# Sheet_Top_Back.net
KiCad netlist of a schematic drawn in Altium Designer
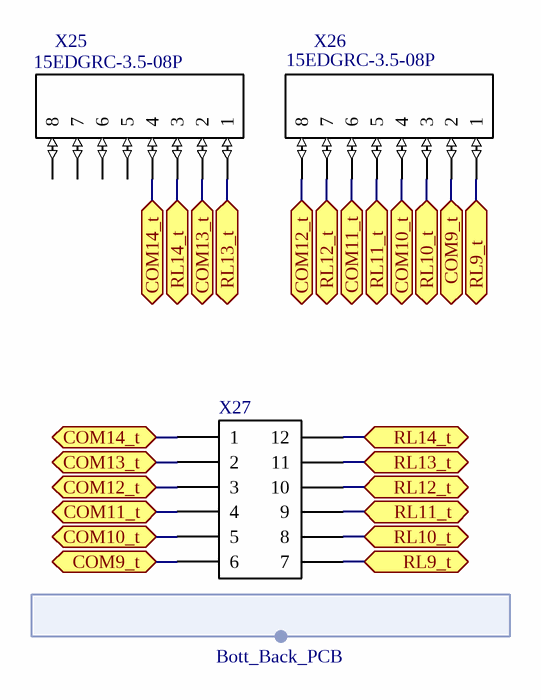
[diagram p0: Sheet_Top_Back.SchDoc]

(export (version "E")
  (design (tool "Eeschema 10.0.6"))
  (components
    (comp (ref "X25")
      (value "15EDGRC-3.5-08P")
      (footprint "MC_3.5_8")
      (description "Connector 3.5mm")
      (libsource (lib "Connect") (part "MC_3.5_8"))
    )
    (comp (ref "X26")
      (value "15EDGRC-3.5-08P")
      (footprint "MC_3.5_8")
      (description "Connector 3.5mm")
      (libsource (lib "Connect") (part "MC_3.5_8"))
    )
    (comp (ref "X27")
      (value "PBS2-12")
      (footprint "PLS2-12")
      (description "Header, 12-Pin")
      (libsource (lib "Connect") (part "PLS2-12"))
    )
  )
  (nets
    (net (code "1") (name "/COM9_t") (class "Default")
      (node (ref "X26") (pin "2") (pinfunction "2_2") (pintype "bidirectional"))
      (node (ref "X27") (pin "6") (pinfunction "6_6") (pintype "passive"))
    )
    (net (code "2") (name "/COM10_t") (class "Default")
      (node (ref "X26") (pin "4") (pinfunction "4_4") (pintype "bidirectional"))
      (node (ref "X27") (pin "5") (pinfunction "5_5") (pintype "passive"))
    )
    (net (code "3") (name "/COM11_t") (class "Default")
      (node (ref "X26") (pin "6") (pinfunction "6_6") (pintype "bidirectional"))
      (node (ref "X27") (pin "4") (pinfunction "4_4") (pintype "passive"))
    )
    (net (code "4") (name "/COM12_t") (class "Default")
      (node (ref "X26") (pin "8") (pinfunction "8_8") (pintype "bidirectional"))
      (node (ref "X27") (pin "3") (pinfunction "3_3") (pintype "passive"))
    )
    (net (code "5") (name "/COM13_t") (class "Default")
      (node (ref "X25") (pin "2") (pinfunction "2_2") (pintype "bidirectional"))
      (node (ref "X27") (pin "2") (pinfunction "2_2") (pintype "passive"))
    )
    (net (code "6") (name "/COM14_t") (class "Default")
      (node (ref "X25") (pin "4") (pinfunction "4_4") (pintype "bidirectional"))
      (node (ref "X27") (pin "1") (pinfunction "1_1") (pintype "passive"))
    )
    (net (code "7") (name "/RL9_t") (class "Default")
      (node (ref "X26") (pin "1") (pinfunction "1_1") (pintype "bidirectional"))
      (node (ref "X27") (pin "7") (pinfunction "7_7") (pintype "passive"))
    )
    (net (code "8") (name "/RL10_t") (class "Default")
      (node (ref "X26") (pin "3") (pinfunction "3_3") (pintype "bidirectional"))
      (node (ref "X27") (pin "8") (pinfunction "8_8") (pintype "passive"))
    )
    (net (code "9") (name "/RL11_t") (class "Default")
      (node (ref "X26") (pin "5") (pinfunction "5_5") (pintype "bidirectional"))
      (node (ref "X27") (pin "9") (pinfunction "9_9") (pintype "passive"))
    )
    (net (code "10") (name "/RL12_t") (class "Default")
      (node (ref "X26") (pin "7") (pinfunction "7_7") (pintype "bidirectional"))
      (node (ref "X27") (pin "10") (pinfunction "10_10") (pintype "passive"))
    )
    (net (code "11") (name "/RL13_t") (class "Default")
      (node (ref "X25") (pin "1") (pinfunction "1_1") (pintype "bidirectional"))
      (node (ref "X27") (pin "11") (pinfunction "11_11") (pintype "passive"))
    )
    (net (code "12") (name "/RL14_t") (class "Default")
      (node (ref "X25") (pin "3") (pinfunction "3_3") (pintype "bidirectional"))
      (node (ref "X27") (pin "12") (pinfunction "12_12") (pintype "passive"))
    )
    (net (code "13") (name "unconnected-(X25-Pad5)") (class "Default")
      (node (ref "X25") (pin "5") (pinfunction "5_5") (pintype "bidirectional"))
    )
    (net (code "14") (name "unconnected-(X25-Pad6)") (class "Default")
      (node (ref "X25") (pin "6") (pinfunction "6_6") (pintype "bidirectional"))
    )
    (net (code "15") (name "unconnected-(X25-Pad7)") (class "Default")
      (node (ref "X25") (pin "7") (pinfunction "7_7") (pintype "bidirectional"))
    )
    (net (code "16") (name "unconnected-(X25-Pad8)") (class "Default")
      (node (ref "X25") (pin "8") (pinfunction "8_8") (pintype "bidirectional"))
    )
  )
)
